# uno_i2c_ntc.net
KiCad netlist of a schematic drawn in EAGLE
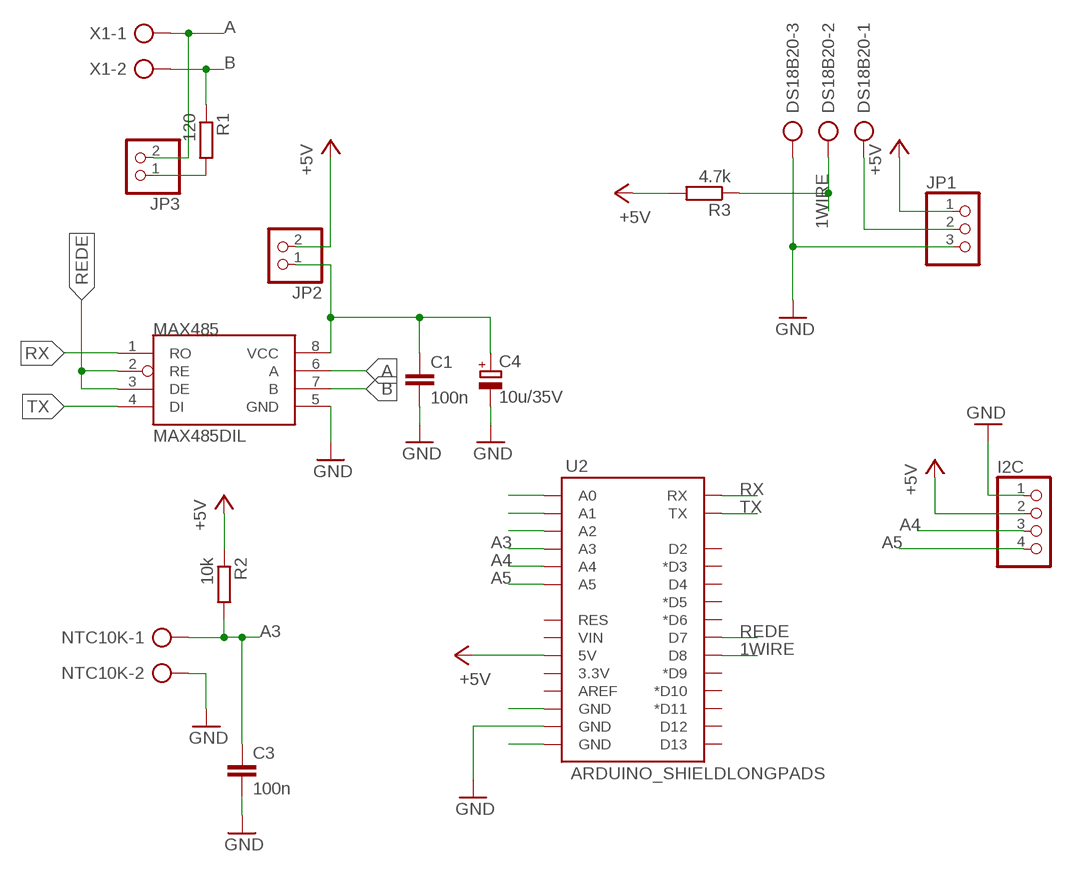
[diagram p0: schematic, sheet 1]

(export (version "E")
  (design (tool "Eeschema 10.0.6"))
  (components
    (comp (ref "C1")
      (value "100n")
      (footprint "eagle-import:C025-024X044")
      (libsource (lib "eagle-import") (part "C-EU025-024X044"))
    )
    (comp (ref "C3")
      (value "100n")
      (footprint "eagle-import:C025-024X044")
      (libsource (lib "eagle-import") (part "C-EU025-024X044"))
    )
    (comp (ref "C4")
      (value "10u/35V")
      (footprint "eagle-import:E2,5-5")
      (libsource (lib "eagle-import") (part "CPOL-EUE2.5-5"))
    )
    (comp (ref "DS18B20")
      (value "AK500/3")
      (footprint "eagle-import:AK500_3")
      (libsource (lib "eagle-import") (part "AK500/3"))
    )
    (comp (ref "I2C")
      (value "PINHD-1X4/90")
      (footprint "eagle-import:1X04_90")
      (libsource (lib "eagle-import") (part "PINHD-1X4/90"))
    )
    (comp (ref "JP1")
      (value "PINHD-1X3")
      (footprint "eagle-import:1X03")
      (libsource (lib "eagle-import") (part "PINHD-1X3"))
    )
    (comp (ref "JP2")
      (value "PINHD-1X2")
      (footprint "eagle-import:1X02")
      (libsource (lib "eagle-import") (part "PINHD-1X2"))
    )
    (comp (ref "JP3")
      (value "PINHD-1X2")
      (footprint "eagle-import:1X02")
      (libsource (lib "eagle-import") (part "PINHD-1X2"))
    )
    (comp (ref "MAX485")
      (value "MAX485DIL")
      (footprint "eagle-import:DIL08")
      (libsource (lib "eagle-import") (part "MAX485DIL"))
    )
    (comp (ref "NTC10K")
      (value "AK500/2")
      (footprint "eagle-import:AK500_2")
      (libsource (lib "eagle-import") (part "AK500/2"))
    )
    (comp (ref "R1")
      (value "120")
      (footprint "eagle-import:0207_10")
      (libsource (lib "eagle-import") (part "R-EU_0207/10"))
    )
    (comp (ref "R2")
      (value "10k")
      (footprint "eagle-import:0207_10")
      (libsource (lib "eagle-import") (part "R-EU_0207/10"))
    )
    (comp (ref "R3")
      (value "4.7k")
      (footprint "eagle-import:0207_10")
      (libsource (lib "eagle-import") (part "R-EU_0207/10"))
    )
    (comp (ref "U2")
      (value "ARDUINO_SHIELDLONGPADS")
      (footprint "eagle-import:DUEMILANOVE_SHIELD_LONGPADS")
      (libsource (lib "eagle-import") (part "ARDUINO_SHIELDLONGPADS"))
    )
    (comp (ref "X1")
      (value "AK500/2")
      (footprint "eagle-import:AK500_2")
      (libsource (lib "eagle-import") (part "AK500/2"))
    )
  )
  (nets
    (net (code "1") (name "+5V") (class "Default")
      (node (ref "I2C") (pin "2") (pinfunction "2_2") (pintype "passive"))
      (node (ref "JP1") (pin "1") (pinfunction "1_1") (pintype "passive"))
      (node (ref "JP2") (pin "2") (pinfunction "2_2") (pintype "passive"))
      (node (ref "R2") (pin "1") (pinfunction "1_1") (pintype "passive"))
      (node (ref "R3") (pin "2") (pinfunction "2_2") (pintype "passive"))
      (node (ref "U2") (pin "5V") (pinfunction "5V_5V") (pintype "bidirectional"))
    )
    (net (code "2") (name "/1WIRE") (class "Default")
      (node (ref "DS18B20") (pin "2") (pinfunction "KL_2") (pintype "passive"))
      (node (ref "R3") (pin "1") (pinfunction "1_1") (pintype "passive"))
      (node (ref "U2") (pin "D8") (pinfunction "D8_D8") (pintype "bidirectional"))
    )
    (net (code "3") (name "/A3") (class "Default")
      (node (ref "C3") (pin "1") (pinfunction "1_1") (pintype "passive"))
      (node (ref "NTC10K") (pin "1") (pinfunction "KL_1") (pintype "passive"))
      (node (ref "R2") (pin "2") (pinfunction "2_2") (pintype "passive"))
      (node (ref "U2") (pin "A3") (pinfunction "A3_A3") (pintype "bidirectional"))
    )
    (net (code "4") (name "/A4") (class "Default")
      (node (ref "I2C") (pin "3") (pinfunction "3_3") (pintype "passive"))
      (node (ref "U2") (pin "A4") (pinfunction "A4_A4") (pintype "bidirectional"))
    )
    (net (code "5") (name "/A5") (class "Default")
      (node (ref "I2C") (pin "4") (pinfunction "4_4") (pintype "passive"))
      (node (ref "U2") (pin "A5") (pinfunction "A5_A5") (pintype "bidirectional"))
    )
    (net (code "6") (name "A") (class "Default")
      (node (ref "JP3") (pin "2") (pinfunction "2_2") (pintype "passive"))
      (node (ref "MAX485") (pin "6") (pinfunction "A_6") (pintype "bidirectional"))
      (node (ref "X1") (pin "1") (pinfunction "KL_1") (pintype "passive"))
    )
    (net (code "7") (name "B") (class "Default")
      (node (ref "MAX485") (pin "7") (pinfunction "B_7") (pintype "bidirectional"))
      (node (ref "R1") (pin "1") (pinfunction "1_1") (pintype "passive"))
      (node (ref "X1") (pin "2") (pinfunction "KL_2") (pintype "passive"))
    )
    (net (code "8") (name "GND") (class "Default")
      (node (ref "C1") (pin "2") (pinfunction "2_2") (pintype "passive"))
      (node (ref "C3") (pin "2") (pinfunction "2_2") (pintype "passive"))
      (node (ref "C4") (pin "-") (pinfunction "-_-") (pintype "passive"))
      (node (ref "DS18B20") (pin "3") (pinfunction "KL_3") (pintype "passive"))
      (node (ref "I2C") (pin "1") (pinfunction "1_1") (pintype "passive"))
      (node (ref "JP1") (pin "3") (pinfunction "3_3") (pintype "passive"))
      (node (ref "MAX485") (pin "5") (pinfunction "GND_5") (pintype "bidirectional"))
      (node (ref "NTC10K") (pin "2") (pinfunction "KL_2") (pintype "passive"))
      (node (ref "U2") (pin "GND@0") (pinfunction "GND_GND@0") (pintype "bidirectional"))
      (node (ref "U2") (pin "GND@1") (pinfunction "GND_GND@1") (pintype "bidirectional"))
      (node (ref "U2") (pin "GND@2") (pinfunction "GND_GND@2") (pintype "bidirectional"))
    )
    (net (code "9") (name "Net-(DS18B20A-KL)") (class "Default")
      (node (ref "DS18B20") (pin "1") (pinfunction "KL_1") (pintype "passive"))
      (node (ref "JP1") (pin "2") (pinfunction "2_2") (pintype "passive"))
    )
    (net (code "10") (name "Net-(JP3-Pad1)") (class "Default")
      (node (ref "JP3") (pin "1") (pinfunction "1_1") (pintype "passive"))
      (node (ref "R1") (pin "2") (pinfunction "2_2") (pintype "passive"))
    )
    (net (code "11") (name "Net-(MAX485-VCC)") (class "Default")
      (node (ref "C1") (pin "1") (pinfunction "1_1") (pintype "passive"))
      (node (ref "C4") (pin "+") (pinfunction "+_+") (pintype "passive"))
      (node (ref "JP2") (pin "1") (pinfunction "1_1") (pintype "passive"))
      (node (ref "MAX485") (pin "8") (pinfunction "VCC_8") (pintype "bidirectional"))
    )
    (net (code "12") (name "REDE") (class "Default")
      (node (ref "MAX485") (pin "2") (pinfunction "RE_2") (pintype "bidirectional"))
      (node (ref "MAX485") (pin "3") (pinfunction "DE_3") (pintype "bidirectional"))
      (node (ref "U2") (pin "D7") (pinfunction "D7_D7") (pintype "bidirectional"))
    )
    (net (code "13") (name "RX") (class "Default")
      (node (ref "MAX485") (pin "1") (pinfunction "RO_1") (pintype "bidirectional"))
      (node (ref "U2") (pin "RX") (pinfunction "RX_RX") (pintype "bidirectional"))
    )
    (net (code "14") (name "TX") (class "Default")
      (node (ref "MAX485") (pin "4") (pinfunction "DI_4") (pintype "bidirectional"))
      (node (ref "U2") (pin "TX") (pinfunction "TX_TX") (pintype "bidirectional"))
    )
    (net (code "15") (name "unconnected-(U2-*D3-PadD3)") (class "Default")
      (node (ref "U2") (pin "D3") (pinfunction "*D3_D3") (pintype "bidirectional"))
    )
    (net (code "16") (name "unconnected-(U2-*D5-PadD5)") (class "Default")
      (node (ref "U2") (pin "D5") (pinfunction "*D5_D5") (pintype "bidirectional"))
    )
    (net (code "17") (name "unconnected-(U2-*D6-PadD6)") (class "Default")
      (node (ref "U2") (pin "D6") (pinfunction "*D6_D6") (pintype "bidirectional"))
    )
    (net (code "18") (name "unconnected-(U2-*D9-PadD9)") (class "Default")
      (node (ref "U2") (pin "D9") (pinfunction "*D9_D9") (pintype "bidirectional"))
    )
    (net (code "19") (name "unconnected-(U2-*D10-PadD10)") (class "Default")
      (node (ref "U2") (pin "D10") (pinfunction "*D10_D10") (pintype "bidirectional"))
    )
    (net (code "20") (name "unconnected-(U2-*D11-PadD11)") (class "Default")
      (node (ref "U2") (pin "D11") (pinfunction "*D11_D11") (pintype "bidirectional"))
    )
    (net (code "21") (name "unconnected-(U2-Pad3.3V)") (class "Default")
      (node (ref "U2") (pin "3.3V") (pinfunction "3.3V_3.3V") (pintype "bidirectional"))
    )
    (net (code "22") (name "unconnected-(U2-PadA0)") (class "Default")
      (node (ref "U2") (pin "A0") (pinfunction "A0_A0") (pintype "bidirectional"))
    )
    (net (code "23") (name "unconnected-(U2-PadA1)") (class "Default")
      (node (ref "U2") (pin "A1") (pinfunction "A1_A1") (pintype "bidirectional"))
    )
    (net (code "24") (name "unconnected-(U2-PadA2)") (class "Default")
      (node (ref "U2") (pin "A2") (pinfunction "A2_A2") (pintype "bidirectional"))
    )
    (net (code "25") (name "unconnected-(U2-PadAREF)") (class "Default")
      (node (ref "U2") (pin "AREF") (pinfunction "AREF_AREF") (pintype "bidirectional"))
    )
    (net (code "26") (name "unconnected-(U2-PadD2)") (class "Default")
      (node (ref "U2") (pin "D2") (pinfunction "D2_D2") (pintype "bidirectional"))
    )
    (net (code "27") (name "unconnected-(U2-PadD4)") (class "Default")
      (node (ref "U2") (pin "D4") (pinfunction "D4_D4") (pintype "bidirectional"))
    )
    (net (code "28") (name "unconnected-(U2-PadD12)") (class "Default")
      (node (ref "U2") (pin "D12") (pinfunction "D12_D12") (pintype "bidirectional"))
    )
    (net (code "29") (name "unconnected-(U2-PadD13)") (class "Default")
      (node (ref "U2") (pin "D13") (pinfunction "D13_D13") (pintype "bidirectional"))
    )
    (net (code "30") (name "unconnected-(U2-PadRES)") (class "Default")
      (node (ref "U2") (pin "RES") (pinfunction "RES_RES") (pintype "bidirectional"))
    )
    (net (code "31") (name "unconnected-(U2-PadVIN)") (class "Default")
      (node (ref "U2") (pin "VIN") (pinfunction "VIN_VIN") (pintype "bidirectional"))
    )
  )
)
